# J006330_DualLickCompREVC.net
KiCad netlist of a schematic drawn in EAGLE
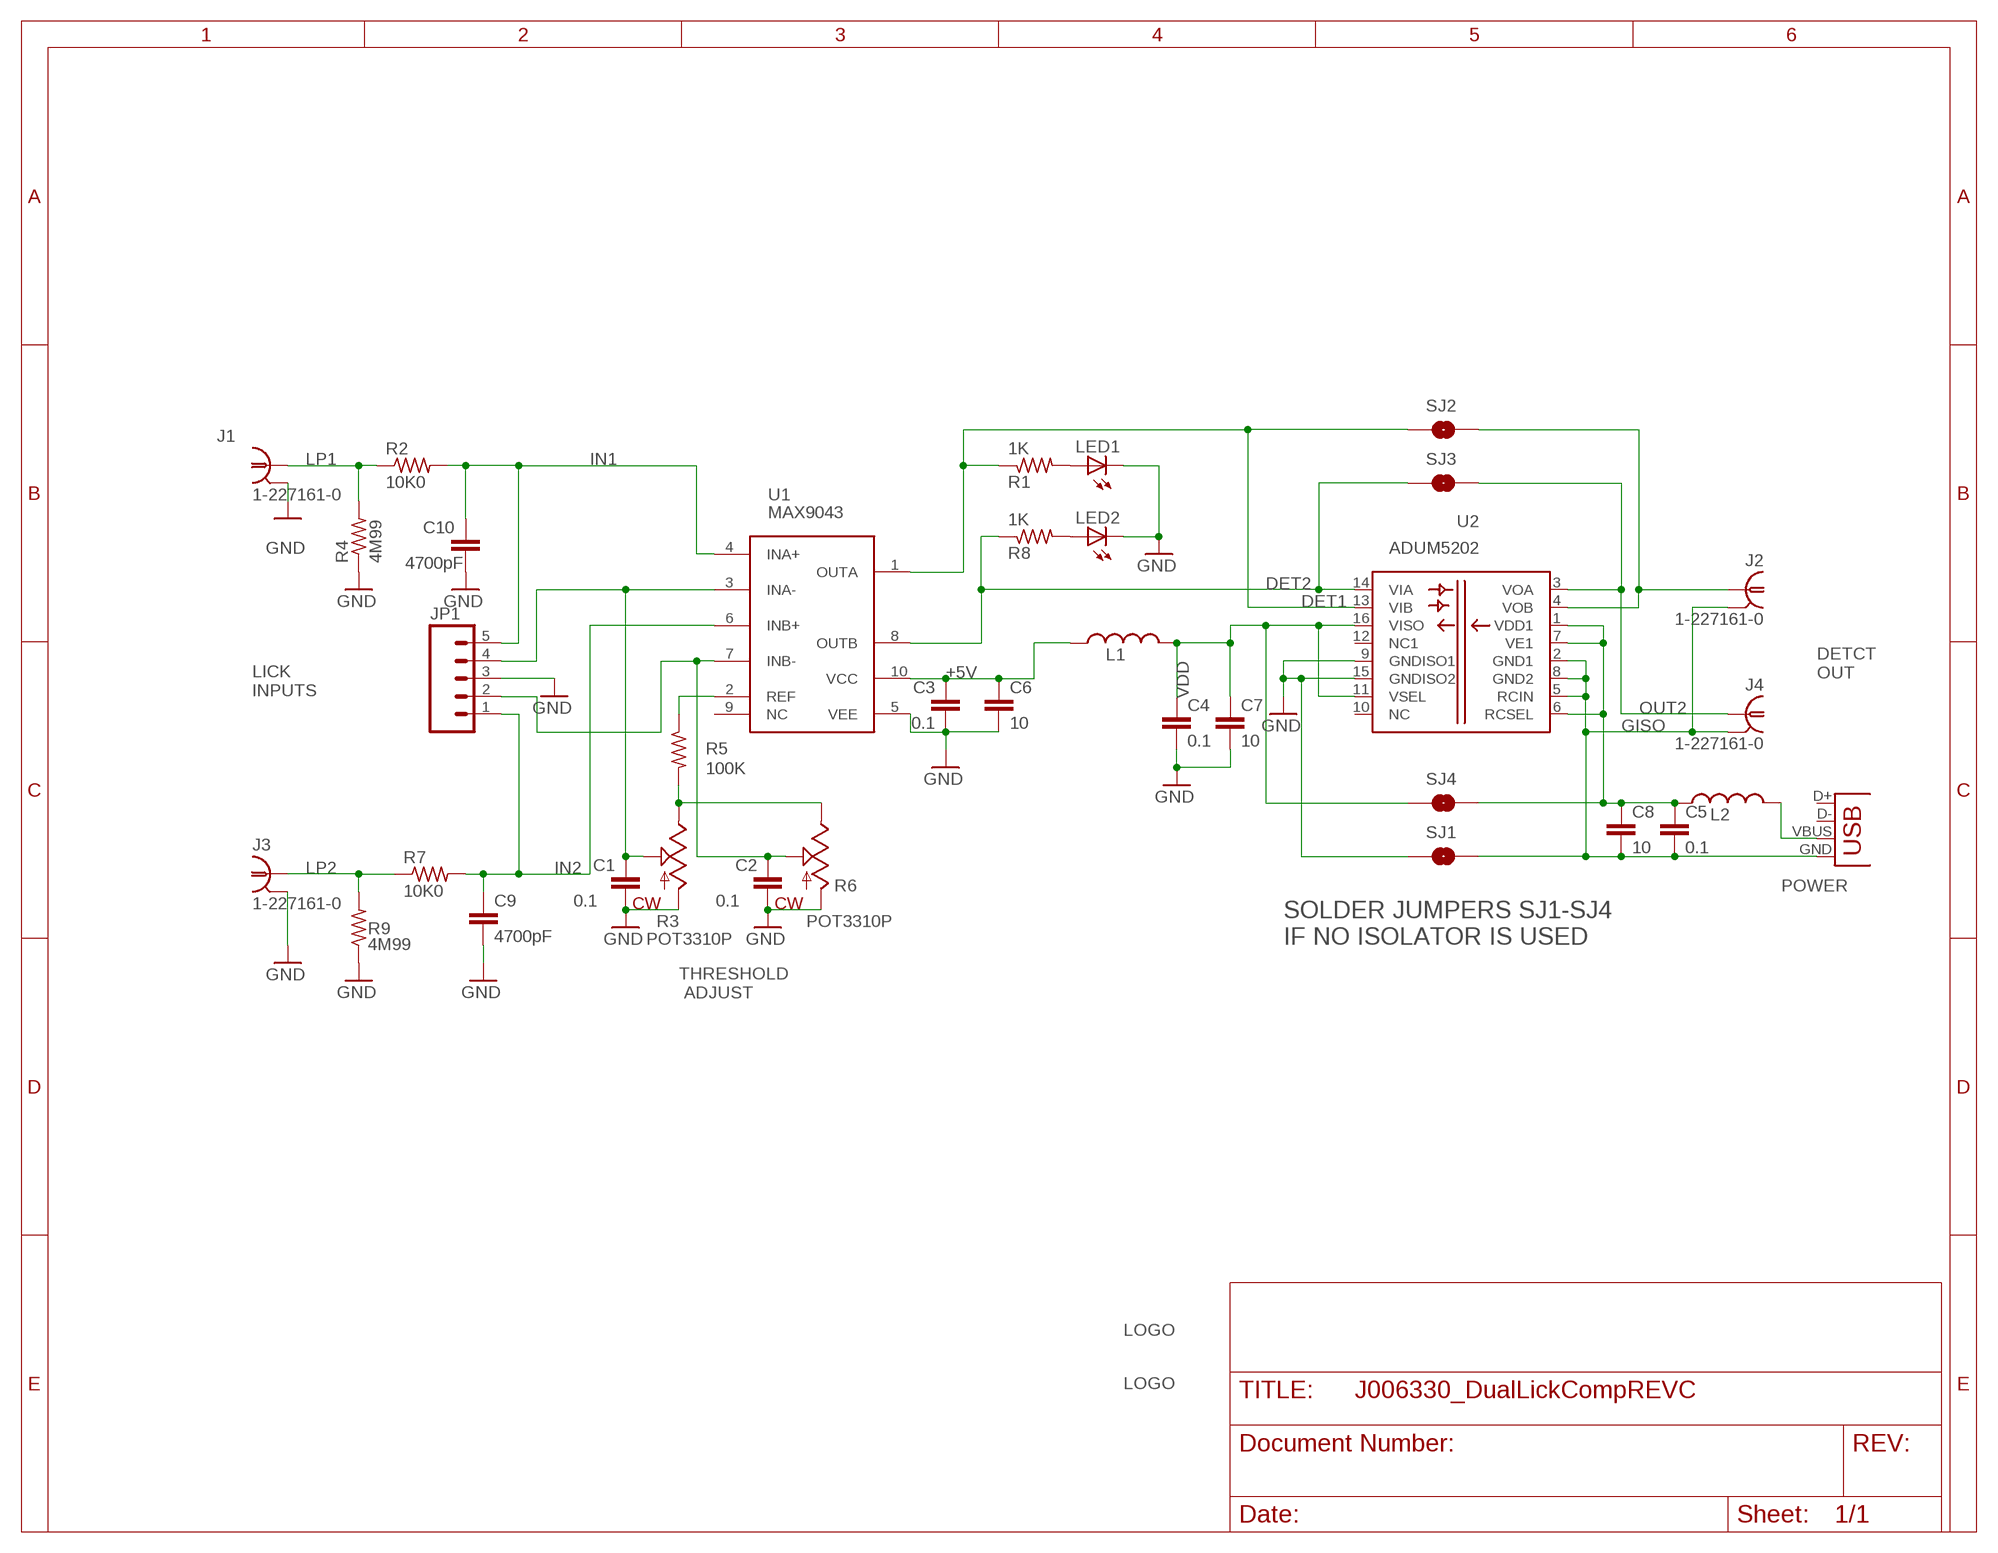
[diagram p0: schematic, sheet 1]

(export (version "E")
  (design (tool "Eeschema 10.0.6"))
  (components
    (comp (ref "C1")
      (value "0.1")
      (footprint "eagle-import:0603S")
      (libsource (lib "eagle-import") (part "CAPS0603S"))
    )
    (comp (ref "C2")
      (value "0.1")
      (footprint "eagle-import:0603S")
      (libsource (lib "eagle-import") (part "CAPS0603S"))
    )
    (comp (ref "C3")
      (value "0.1")
      (footprint "eagle-import:0603S")
      (libsource (lib "eagle-import") (part "CAPS0603S"))
    )
    (comp (ref "C4")
      (value "0.1")
      (footprint "eagle-import:0603S")
      (libsource (lib "eagle-import") (part "CAPS0603S"))
    )
    (comp (ref "C5")
      (value "0.1")
      (footprint "eagle-import:0603S")
      (libsource (lib "eagle-import") (part "CAPS0603S"))
    )
    (comp (ref "C6")
      (value "10")
      (footprint "eagle-import:0805S")
      (libsource (lib "eagle-import") (part "CAPS0805S"))
    )
    (comp (ref "C7")
      (value "10")
      (footprint "eagle-import:0805S")
      (libsource (lib "eagle-import") (part "CAPS0805S"))
    )
    (comp (ref "C8")
      (value "10")
      (footprint "eagle-import:0805S")
      (libsource (lib "eagle-import") (part "CAPS0805S"))
    )
    (comp (ref "C9")
      (value "4700pF")
      (footprint "eagle-import:0805S")
      (libsource (lib "eagle-import") (part "CAPS0805S"))
    )
    (comp (ref "C10")
      (value "4700pF")
      (footprint "eagle-import:0805S")
      (libsource (lib "eagle-import") (part "CAPS0805S"))
    )
    (comp (ref "J1")
      (value "1-227161-0")
      (footprint "eagle-import:AMP_227161")
      (fields (field (name "MF") "TYCO ELECTRONICS") (field (name "MPN") "1-227161"))
      (libsource (lib "eagle-import") (part "?2271611--0"))
    )
    (comp (ref "J2")
      (value "1-227161-0")
      (footprint "eagle-import:AMP_227161")
      (fields (field (name "MF") "TYCO ELECTRONICS") (field (name "MPN") "1-227161"))
      (libsource (lib "eagle-import") (part "?2271611--0"))
    )
    (comp (ref "J3")
      (value "1-227161-0")
      (footprint "eagle-import:AMP_227161")
      (fields (field (name "MF") "TYCO ELECTRONICS") (field (name "MPN") "1-227161"))
      (libsource (lib "eagle-import") (part "?2271611--0"))
    )
    (comp (ref "J4")
      (value "1-227161-0")
      (footprint "eagle-import:AMP_227161")
      (fields (field (name "MF") "TYCO ELECTRONICS") (field (name "MPN") "1-227161"))
      (libsource (lib "eagle-import") (part "?2271611--0"))
    )
    (comp (ref "J100")
      (value "USB")
      (footprint "eagle-import:10118194")
      (libsource (lib "eagle-import") (part "USB"))
    )
    (comp (ref "JP1")
      (value "M05LOCK")
      (footprint "eagle-import:1X05_LOCK")
      (libsource (lib "eagle-import") (part "M05LOCK"))
    )
    (comp (ref "L1")
      (value "INDUCTOR_SM0805S")
      (footprint "eagle-import:0805S")
      (libsource (lib "eagle-import") (part "INDUCTOR_SM0805S"))
    )
    (comp (ref "L2")
      (value "INDUCTOR_SM0805S")
      (footprint "eagle-import:0805S")
      (libsource (lib "eagle-import") (part "INDUCTOR_SM0805S"))
    )
    (comp (ref "LED1")
      (value "LED5MM")
      (footprint "eagle-import:LED5MM")
      (libsource (lib "eagle-import") (part "LED5MM"))
    )
    (comp (ref "LED2")
      (value "LED5MM")
      (footprint "eagle-import:LED5MM")
      (libsource (lib "eagle-import") (part "LED5MM"))
    )
    (comp (ref "R1")
      (value "1K")
      (footprint "eagle-import:0805S")
      (libsource (lib "eagle-import") (part "RESISTOR_SM0805S"))
    )
    (comp (ref "R2")
      (value "10K0")
      (footprint "eagle-import:0805S")
      (libsource (lib "eagle-import") (part "RESISTOR_SM0805S"))
    )
    (comp (ref "R3")
      (value "POT3310P")
      (footprint "eagle-import:3310P")
      (libsource (lib "eagle-import") (part "POT3310P"))
    )
    (comp (ref "R4")
      (value "4M99")
      (footprint "eagle-import:0805S")
      (libsource (lib "eagle-import") (part "RESISTOR_SM0805S"))
    )
    (comp (ref "R5")
      (value "100K")
      (footprint "eagle-import:0805S")
      (libsource (lib "eagle-import") (part "RESISTOR_SM0805S"))
    )
    (comp (ref "R6")
      (value "POT3310P")
      (footprint "eagle-import:3310P")
      (libsource (lib "eagle-import") (part "POT3310P"))
    )
    (comp (ref "R7")
      (value "10K0")
      (footprint "eagle-import:0805S")
      (libsource (lib "eagle-import") (part "RESISTOR_SM0805S"))
    )
    (comp (ref "R8")
      (value "1K")
      (footprint "eagle-import:0805S")
      (libsource (lib "eagle-import") (part "RESISTOR_SM0805S"))
    )
    (comp (ref "R9")
      (value "4M99")
      (footprint "eagle-import:0805S")
      (libsource (lib "eagle-import") (part "RESISTOR_SM0805S"))
    )
    (comp (ref "SJ1")
      (value "SOLDERJUMPERNO")
      (footprint "eagle-import:SJ_2S-NO")
      (libsource (lib "eagle-import") (part "SOLDERJUMPERNO"))
    )
    (comp (ref "SJ2")
      (value "SOLDERJUMPERNO")
      (footprint "eagle-import:SJ_2S-NO")
      (libsource (lib "eagle-import") (part "SOLDERJUMPERNO"))
    )
    (comp (ref "SJ3")
      (value "SOLDERJUMPERNO")
      (footprint "eagle-import:SJ_2S-NO")
      (libsource (lib "eagle-import") (part "SOLDERJUMPERNO"))
    )
    (comp (ref "SJ4")
      (value "SOLDERJUMPERNO")
      (footprint "eagle-import:SJ_2S-NO")
      (libsource (lib "eagle-import") (part "SOLDERJUMPERNO"))
    )
    (comp (ref "U$1")
      (value "JFRC-LOGOLOGO_OP")
      (footprint "eagle-import:LOGO_BMP_OP")
      (libsource (lib "eagle-import") (part "JFRC-LOGOLOGO_OP"))
    )
    (comp (ref "U$2")
      (value "JFRC-LOGOLOGO_JANELIA_2014_ECLOSURE")
      (footprint "eagle-import:LOGO_JANELIA_2014_ENCLOSURE")
      (libsource (lib "eagle-import") (part "JFRC-LOGOLOGO_JANELIA_2014_ECLOSURE"))
    )
    (comp (ref "U1")
      (value "MAX9043")
      (footprint "eagle-import:UMAX10")
      (libsource (lib "eagle-import") (part "MAX9043"))
    )
    (comp (ref "U2")
      (value "ADUM5202")
      (footprint "eagle-import:SO-16-7.5MM")
      (libsource (lib "eagle-import") (part "ADUM5202"))
    )
  )
  (nets
    (net (code "1") (name "/+5V") (class "Default")
      (node (ref "C3") (pin "1") (pinfunction "1_1") (pintype "passive"))
      (node (ref "C6") (pin "1") (pinfunction "1_1") (pintype "passive"))
      (node (ref "L1") (pin "1") (pinfunction "1_1") (pintype "passive"))
      (node (ref "U1") (pin "10") (pinfunction "VCC_10") (pintype "bidirectional"))
    )
    (net (code "2") (name "/DET1") (class "Default")
      (node (ref "R1") (pin "1") (pinfunction "1_1") (pintype "passive"))
      (node (ref "SJ2") (pin "1") (pinfunction "1_1") (pintype "passive"))
      (node (ref "U1") (pin "1") (pinfunction "OUTA_1") (pintype "bidirectional"))
      (node (ref "U2") (pin "13") (pinfunction "VIB_13") (pintype "tri_state"))
    )
    (net (code "3") (name "/DET2") (class "Default")
      (node (ref "R8") (pin "1") (pinfunction "1_1") (pintype "passive"))
      (node (ref "SJ3") (pin "1") (pinfunction "1_1") (pintype "passive"))
      (node (ref "U1") (pin "8") (pinfunction "OUTB_8") (pintype "bidirectional"))
      (node (ref "U2") (pin "14") (pinfunction "VIA_14") (pintype "input"))
    )
    (net (code "4") (name "/GISO") (class "Default")
      (node (ref "C5") (pin "2") (pinfunction "2_2") (pintype "passive"))
      (node (ref "C8") (pin "2") (pinfunction "2_2") (pintype "passive"))
      (node (ref "J100") (pin "GND") (pinfunction "GND_GND") (pintype "bidirectional"))
      (node (ref "J2") (pin "2") (pinfunction "2_2") (pintype "passive"))
      (node (ref "J4") (pin "2") (pinfunction "2_2") (pintype "passive"))
      (node (ref "SJ1") (pin "2") (pinfunction "2_2") (pintype "passive"))
      (node (ref "U2") (pin "2") (pinfunction "GND1_2") (pintype "input"))
      (node (ref "U2") (pin "5") (pinfunction "RCIN_5") (pintype "bidirectional"))
      (node (ref "U2") (pin "8") (pinfunction "GND2_8") (pintype "bidirectional"))
    )
    (net (code "5") (name "/IN1") (class "Default")
      (node (ref "C10") (pin "1") (pinfunction "1_1") (pintype "passive"))
      (node (ref "JP1") (pin "5") (pinfunction "5_5") (pintype "passive"))
      (node (ref "R2") (pin "2") (pinfunction "2_2") (pintype "passive"))
      (node (ref "U1") (pin "4") (pinfunction "INA+_4") (pintype "bidirectional"))
    )
    (net (code "6") (name "/IN2") (class "Default")
      (node (ref "C9") (pin "1") (pinfunction "1_1") (pintype "passive"))
      (node (ref "JP1") (pin "1") (pinfunction "1_1") (pintype "passive"))
      (node (ref "R7") (pin "2") (pinfunction "2_2") (pintype "passive"))
      (node (ref "U1") (pin "6") (pinfunction "INB+_6") (pintype "bidirectional"))
    )
    (net (code "7") (name "/LP1") (class "Default")
      (node (ref "J1") (pin "1") (pinfunction "1_1") (pintype "passive"))
      (node (ref "R2") (pin "1") (pinfunction "1_1") (pintype "passive"))
      (node (ref "R4") (pin "2") (pinfunction "2_2") (pintype "passive"))
    )
    (net (code "8") (name "/LP2") (class "Default")
      (node (ref "J3") (pin "1") (pinfunction "1_1") (pintype "passive"))
      (node (ref "R7") (pin "1") (pinfunction "1_1") (pintype "passive"))
      (node (ref "R9") (pin "2") (pinfunction "2_2") (pintype "passive"))
    )
    (net (code "9") (name "/OUT2") (class "Default")
      (node (ref "J4") (pin "1") (pinfunction "1_1") (pintype "passive"))
      (node (ref "SJ3") (pin "2") (pinfunction "2_2") (pintype "passive"))
      (node (ref "U2") (pin "3") (pinfunction "VOA_3") (pintype "tri_state"))
    )
    (net (code "10") (name "/VDD") (class "Default")
      (node (ref "C4") (pin "1") (pinfunction "1_1") (pintype "passive"))
      (node (ref "C7") (pin "1") (pinfunction "1_1") (pintype "passive"))
      (node (ref "L1") (pin "2") (pinfunction "2_2") (pintype "passive"))
      (node (ref "SJ4") (pin "1") (pinfunction "1_1") (pintype "passive"))
      (node (ref "U2") (pin "11") (pinfunction "VSEL_11") (pintype "bidirectional"))
      (node (ref "U2") (pin "16") (pinfunction "VISO_16") (pintype "input"))
    )
    (net (code "11") (name "GND") (class "Default")
      (node (ref "C1") (pin "2") (pinfunction "2_2") (pintype "passive"))
      (node (ref "C10") (pin "2") (pinfunction "2_2") (pintype "passive"))
      (node (ref "C2") (pin "2") (pinfunction "2_2") (pintype "passive"))
      (node (ref "C3") (pin "2") (pinfunction "2_2") (pintype "passive"))
      (node (ref "C4") (pin "2") (pinfunction "2_2") (pintype "passive"))
      (node (ref "C6") (pin "2") (pinfunction "2_2") (pintype "passive"))
      (node (ref "C7") (pin "2") (pinfunction "2_2") (pintype "passive"))
      (node (ref "C9") (pin "2") (pinfunction "2_2") (pintype "passive"))
      (node (ref "J1") (pin "2") (pinfunction "2_2") (pintype "passive"))
      (node (ref "J3") (pin "2") (pinfunction "2_2") (pintype "passive"))
      (node (ref "JP1") (pin "3") (pinfunction "3_3") (pintype "passive"))
      (node (ref "LED1") (pin "K") (pinfunction "C_K") (pintype "passive"))
      (node (ref "LED2") (pin "K") (pinfunction "C_K") (pintype "passive"))
      (node (ref "R3") (pin "1") (pinfunction "CCW_1") (pintype "passive"))
      (node (ref "R4") (pin "1") (pinfunction "1_1") (pintype "passive"))
      (node (ref "R6") (pin "1") (pinfunction "CCW_1") (pintype "passive"))
      (node (ref "R9") (pin "1") (pinfunction "1_1") (pintype "passive"))
      (node (ref "SJ1") (pin "1") (pinfunction "1_1") (pintype "passive"))
      (node (ref "U1") (pin "5") (pinfunction "VEE_5") (pintype "bidirectional"))
      (node (ref "U2") (pin "15") (pinfunction "GNDISO2_15") (pintype "bidirectional"))
      (node (ref "U2") (pin "9") (pinfunction "GNDISO1_9") (pintype "input"))
    )
    (net (code "12") (name "Net-(J100-PadVBUS)") (class "Default")
      (node (ref "J100") (pin "VBUS") (pinfunction "VBUS_VBUS") (pintype "bidirectional"))
      (node (ref "L2") (pin "2") (pinfunction "2_2") (pintype "passive"))
    )
    (net (code "13") (name "Net-(LED1-PadA)") (class "Default")
      (node (ref "LED1") (pin "A") (pinfunction "A_A") (pintype "passive"))
      (node (ref "R1") (pin "2") (pinfunction "2_2") (pintype "passive"))
    )
    (net (code "14") (name "Net-(LED2-PadA)") (class "Default")
      (node (ref "LED2") (pin "A") (pinfunction "A_A") (pintype "passive"))
      (node (ref "R8") (pin "2") (pinfunction "2_2") (pintype "passive"))
    )
    (net (code "15") (name "Net-(R3-CW)") (class "Default")
      (node (ref "R3") (pin "3") (pinfunction "CW_3") (pintype "passive"))
      (node (ref "R5") (pin "2") (pinfunction "2_2") (pintype "passive"))
      (node (ref "R6") (pin "3") (pinfunction "CW_3") (pintype "passive"))
    )
    (net (code "16") (name "Net-(R3-W)") (class "Default")
      (node (ref "C1") (pin "1") (pinfunction "1_1") (pintype "passive"))
      (node (ref "JP1") (pin "4") (pinfunction "4_4") (pintype "passive"))
      (node (ref "R3") (pin "2") (pinfunction "W_2") (pintype "passive"))
      (node (ref "U1") (pin "3") (pinfunction "INA-_3") (pintype "bidirectional"))
    )
    (net (code "17") (name "Net-(R6-W)") (class "Default")
      (node (ref "C2") (pin "1") (pinfunction "1_1") (pintype "passive"))
      (node (ref "JP1") (pin "2") (pinfunction "2_2") (pintype "passive"))
      (node (ref "R6") (pin "2") (pinfunction "W_2") (pintype "passive"))
      (node (ref "U1") (pin "7") (pinfunction "INB-_7") (pintype "bidirectional"))
    )
    (net (code "18") (name "Net-(U1-REF)") (class "Default")
      (node (ref "R5") (pin "1") (pinfunction "1_1") (pintype "passive"))
      (node (ref "U1") (pin "2") (pinfunction "REF_2") (pintype "bidirectional"))
    )
    (net (code "19") (name "Net-(U2-RCSEL)") (class "Default")
      (node (ref "C5") (pin "1") (pinfunction "1_1") (pintype "passive"))
      (node (ref "C8") (pin "1") (pinfunction "1_1") (pintype "passive"))
      (node (ref "L2") (pin "1") (pinfunction "1_1") (pintype "passive"))
      (node (ref "SJ4") (pin "2") (pinfunction "2_2") (pintype "passive"))
      (node (ref "U2") (pin "1") (pinfunction "VDD1_1") (pintype "input"))
      (node (ref "U2") (pin "6") (pinfunction "RCSEL_6") (pintype "bidirectional"))
      (node (ref "U2") (pin "7") (pinfunction "VE1_7") (pintype "bidirectional"))
    )
    (net (code "20") (name "Net-(U2-VOB)") (class "Default")
      (node (ref "J2") (pin "1") (pinfunction "1_1") (pintype "passive"))
      (node (ref "SJ2") (pin "2") (pinfunction "2_2") (pintype "passive"))
      (node (ref "U2") (pin "4") (pinfunction "VOB_4") (pintype "input"))
    )
    (net (code "21") (name "unconnected-(J100-PadD+)") (class "Default")
      (node (ref "J100") (pin "D+") (pinfunction "D+_D+") (pintype "bidirectional"))
    )
    (net (code "22") (name "unconnected-(J100-PadD-)") (class "Default")
      (node (ref "J100") (pin "D-") (pinfunction "D-_D-") (pintype "bidirectional"))
    )
    (net (code "23") (name "unconnected-(U1-NC-Pad9)") (class "Default")
      (node (ref "U1") (pin "9") (pinfunction "NC_9") (pintype "bidirectional"))
    )
    (net (code "24") (name "unconnected-(U2-NC-Pad10)") (class "Default")
      (node (ref "U2") (pin "10") (pinfunction "NC_10") (pintype "bidirectional"))
    )
    (net (code "25") (name "unconnected-(U2-NC1-Pad12)") (class "Default")
      (node (ref "U2") (pin "12") (pinfunction "NC1_12") (pintype "bidirectional"))
    )
  )
)
